# SD.net
KiCad netlist of a schematic drawn in Altium Designer
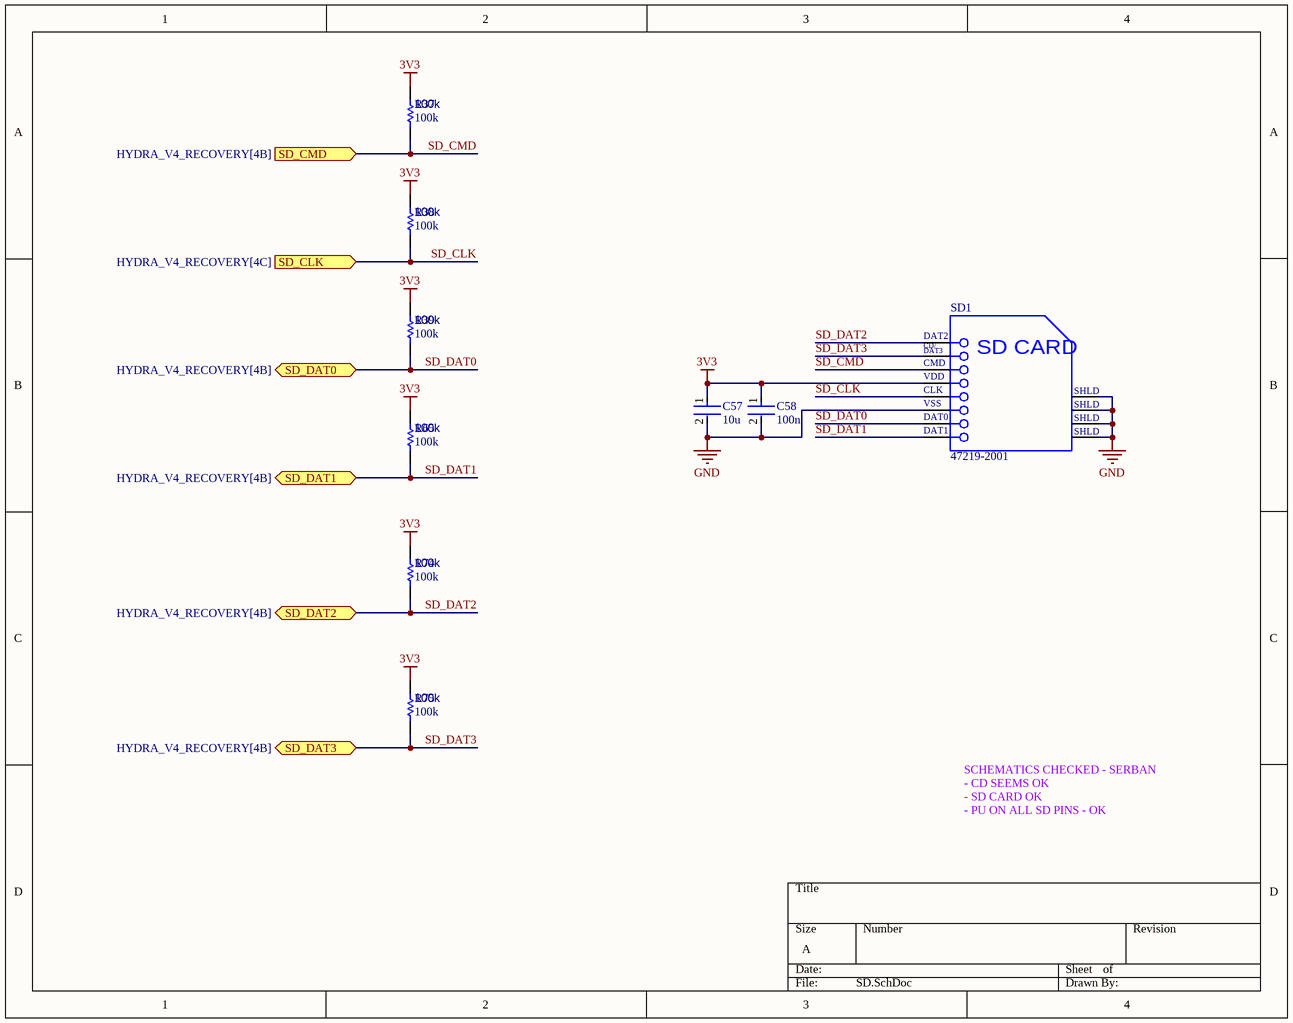
[diagram p0: SD.SchDoc]

(export (version "E")
  (design (tool "Eeschema 10.0.6"))
  (components
    (comp (ref "C57")
      (value "10u")
      (footprint "FP-0402-L_1_0_0_05-W_0_5-IPC_A")
      (description "LARGE PADS, 0402 CAP, CHANGE COMMENT TO MATCH REAL P/N")
      (libsource (lib "Space Concordia") (part "b4654b650e69147ec39a6b967a45e02"))
    )
    (comp (ref "C58")
      (value "100n")
      (footprint "FP-0402-L_1_0_0_05-W_0_5-IPC_A")
      (description "LARGE PADS, 0402 CAP, CHANGE COMMENT TO MATCH REAL P/N")
      (libsource (lib "Space Concordia") (part "b4654b650e69147ec39a6b967a45e02"))
    )
    (comp (ref "R37")
      (value "100k")
      (footprint "R0603B")
      (description "Resistor")
      (fields (field (name "ALTIUM_VALUE") "100k"))
      (libsource (lib "Space Concordia") (part "Resistor"))
    )
    (comp (ref "R38")
      (value "100k")
      (footprint "R0603B")
      (description "Resistor")
      (fields (field (name "ALTIUM_VALUE") "100k"))
      (libsource (lib "Space Concordia") (part "Resistor"))
    )
    (comp (ref "R39")
      (value "100k")
      (footprint "R0603B")
      (description "Resistor")
      (fields (field (name "ALTIUM_VALUE") "100k"))
      (libsource (lib "Space Concordia") (part "Resistor"))
    )
    (comp (ref "R65")
      (value "100k")
      (footprint "R0603B")
      (description "Resistor")
      (fields (field (name "ALTIUM_VALUE") "100k"))
      (libsource (lib "Space Concordia") (part "Resistor"))
    )
    (comp (ref "R74")
      (value "100k")
      (footprint "R0603B")
      (description "Resistor")
      (fields (field (name "ALTIUM_VALUE") "100k"))
      (libsource (lib "Space Concordia") (part "Resistor"))
    )
    (comp (ref "R75")
      (value "100k")
      (footprint "R0603B")
      (description "Resistor")
      (fields (field (name "ALTIUM_VALUE") "100k"))
      (libsource (lib "Space Concordia") (part "Resistor"))
    )
    (comp (ref "SD1")
      (value "47219-2001")
      (footprint "MOLX-47219-2001-8_V")
      (description "MicroSD Card Connector, Hinge Type, -40 to 85 degC, 8-Pin SMD, RoHS, Tape and Reel")
      (fields (field (name "MANUFACTURER") "Molex"))
      (libsource (lib "Altium Content Vault") (part "CN-SD-8-4S"))
    )
  )
  (nets
    (net (code "1") (name "/SD_CLK") (class "Default")
      (node (ref "R38") (pin "2") (pinfunction "2_2") (pintype "passive"))
      (node (ref "SD1") (pin "5") (pinfunction "CLK_5") (pintype "passive"))
    )
    (net (code "2") (name "/SD_CMD") (class "Default")
      (node (ref "R37") (pin "2") (pinfunction "2_2") (pintype "passive"))
      (node (ref "SD1") (pin "3") (pinfunction "CMD_3") (pintype "passive"))
    )
    (net (code "3") (name "/SD_DAT0") (class "Default")
      (node (ref "R39") (pin "2") (pinfunction "2_2") (pintype "passive"))
      (node (ref "SD1") (pin "7") (pinfunction "DAT0_7") (pintype "passive"))
    )
    (net (code "4") (name "/SD_DAT1") (class "Default")
      (node (ref "R65") (pin "2") (pinfunction "2_2") (pintype "passive"))
      (node (ref "SD1") (pin "8") (pinfunction "DAT1_8") (pintype "passive"))
    )
    (net (code "5") (name "/SD_DAT2") (class "Default")
      (node (ref "R74") (pin "2") (pinfunction "2_2") (pintype "passive"))
      (node (ref "SD1") (pin "1") (pinfunction "DAT2_1") (pintype "passive"))
    )
    (net (code "6") (name "/SD_DAT3") (class "Default")
      (node (ref "R75") (pin "2") (pinfunction "2_2") (pintype "passive"))
      (node (ref "SD1") (pin "2") (pinfunction "CD/DAT3_2") (pintype "passive"))
    )
    (net (code "7") (name "3V3") (class "Default")
      (node (ref "C57") (pin "1") (pinfunction "1_1") (pintype "passive"))
      (node (ref "C58") (pin "1") (pinfunction "1_1") (pintype "passive"))
      (node (ref "R37") (pin "1") (pinfunction "1_1") (pintype "passive"))
      (node (ref "R38") (pin "1") (pinfunction "1_1") (pintype "passive"))
      (node (ref "R39") (pin "1") (pinfunction "1_1") (pintype "passive"))
      (node (ref "R65") (pin "1") (pinfunction "1_1") (pintype "passive"))
      (node (ref "R74") (pin "1") (pinfunction "1_1") (pintype "passive"))
      (node (ref "R75") (pin "1") (pinfunction "1_1") (pintype "passive"))
      (node (ref "SD1") (pin "4") (pinfunction "VDD_4") (pintype "passive"))
    )
    (net (code "8") (name "GND") (class "Default")
      (node (ref "C57") (pin "2") (pinfunction "2_2") (pintype "passive"))
      (node (ref "C58") (pin "2") (pinfunction "2_2") (pintype "passive"))
      (node (ref "SD1") (pin "10") (pinfunction "SHLD_10") (pintype "passive"))
      (node (ref "SD1") (pin "11") (pinfunction "SHLD_11") (pintype "passive"))
      (node (ref "SD1") (pin "12") (pinfunction "SHLD_12") (pintype "passive"))
      (node (ref "SD1") (pin "6") (pinfunction "VSS_6") (pintype "passive"))
      (node (ref "SD1") (pin "9") (pinfunction "SHLD_9") (pintype "passive"))
    )
  )
)
